# redLED12V.net
KiCad netlist of a schematic drawn in EAGLE
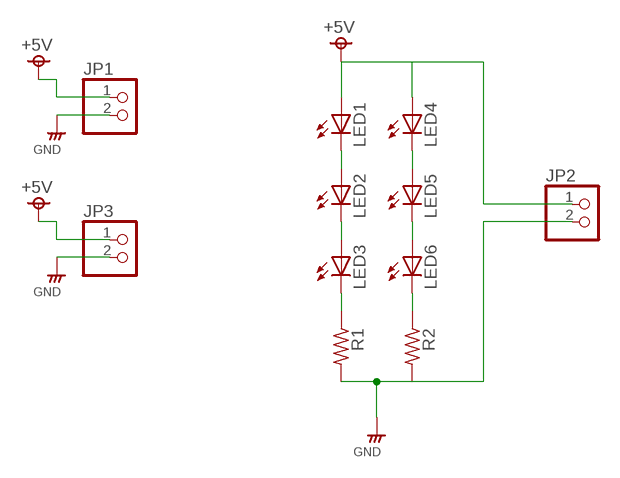
[diagram p0: schematic, sheet 1]

(export (version "E")
  (design (tool "Eeschema 10.0.6"))
  (components
    (comp (ref "JP1")
      (value "PINHD-1X2\"")
      (footprint "eagle-import:1_02")
      (libsource (lib "eagle-import") (part "PINHD-1X2{dblquote}"))
    )
    (comp (ref "JP2")
      (value "PINHD-1X2\"")
      (footprint "eagle-import:1_02")
      (libsource (lib "eagle-import") (part "PINHD-1X2{dblquote}"))
    )
    (comp (ref "JP3")
      (value "PINHD-1X2\"")
      (footprint "eagle-import:1_02")
      (libsource (lib "eagle-import") (part "PINHD-1X2{dblquote}"))
    )
    (comp (ref "LED1")
      (value "LED5MM")
      (footprint "eagle-import:LED5MM")
      (libsource (lib "eagle-import") (part "LED5MM"))
    )
    (comp (ref "LED2")
      (value "LED5MM")
      (footprint "eagle-import:LED5MM")
      (libsource (lib "eagle-import") (part "LED5MM"))
    )
    (comp (ref "LED3")
      (value "LED5MM")
      (footprint "eagle-import:LED5MM")
      (libsource (lib "eagle-import") (part "LED5MM"))
    )
    (comp (ref "LED4")
      (value "LED5MM")
      (footprint "eagle-import:LED5MM")
      (libsource (lib "eagle-import") (part "LED5MM"))
    )
    (comp (ref "LED5")
      (value "LED5MM")
      (footprint "eagle-import:LED5MM")
      (libsource (lib "eagle-import") (part "LED5MM"))
    )
    (comp (ref "LED6")
      (value "LED5MM")
      (footprint "eagle-import:LED5MM")
      (libsource (lib "eagle-import") (part "LED5MM"))
    )
    (comp (ref "R1")
      (value "RESISTORS-3")
      (footprint "eagle-import:R_0.2")
      (libsource (lib "eagle-import") (part "RESISTORS-3"))
    )
    (comp (ref "R2")
      (value "RESISTORS-3")
      (footprint "eagle-import:R_0.2")
      (libsource (lib "eagle-import") (part "RESISTORS-3"))
    )
  )
  (nets
    (net (code "1") (name "/+5V") (class "Default")
      (node (ref "JP1") (pin "1") (pinfunction "1_1") (pintype "passive"))
      (node (ref "JP2") (pin "1") (pinfunction "1_1") (pintype "passive"))
      (node (ref "JP3") (pin "1") (pinfunction "1_1") (pintype "passive"))
      (node (ref "LED1") (pin "A") (pinfunction "A_A") (pintype "passive"))
      (node (ref "LED4") (pin "A") (pinfunction "A_A") (pintype "passive"))
    )
    (net (code "2") (name "GND") (class "Default")
      (node (ref "JP1") (pin "2") (pinfunction "2_2") (pintype "passive"))
      (node (ref "JP2") (pin "2") (pinfunction "2_2") (pintype "passive"))
      (node (ref "JP3") (pin "2") (pinfunction "2_2") (pintype "passive"))
      (node (ref "R1") (pin "2") (pinfunction "2_2") (pintype "passive"))
      (node (ref "R2") (pin "2") (pinfunction "2_2") (pintype "passive"))
    )
    (net (code "3") (name "Net-(LED1-C)") (class "Default")
      (node (ref "LED1") (pin "K") (pinfunction "C_K") (pintype "passive"))
      (node (ref "LED2") (pin "A") (pinfunction "A_A") (pintype "passive"))
    )
    (net (code "4") (name "Net-(LED2-C)") (class "Default")
      (node (ref "LED2") (pin "K") (pinfunction "C_K") (pintype "passive"))
      (node (ref "LED3") (pin "A") (pinfunction "A_A") (pintype "passive"))
    )
    (net (code "5") (name "Net-(LED3-C)") (class "Default")
      (node (ref "LED3") (pin "K") (pinfunction "C_K") (pintype "passive"))
      (node (ref "R1") (pin "1") (pinfunction "1_1") (pintype "passive"))
    )
    (net (code "6") (name "Net-(LED4-C)") (class "Default")
      (node (ref "LED4") (pin "K") (pinfunction "C_K") (pintype "passive"))
      (node (ref "LED5") (pin "A") (pinfunction "A_A") (pintype "passive"))
    )
    (net (code "7") (name "Net-(LED5-C)") (class "Default")
      (node (ref "LED5") (pin "K") (pinfunction "C_K") (pintype "passive"))
      (node (ref "LED6") (pin "A") (pinfunction "A_A") (pintype "passive"))
    )
    (net (code "8") (name "Net-(LED6-C)") (class "Default")
      (node (ref "LED6") (pin "K") (pinfunction "C_K") (pintype "passive"))
      (node (ref "R2") (pin "1") (pinfunction "1_1") (pintype "passive"))
    )
  )
)
